# SIPM_readout.net
KiCad netlist of a schematic drawn in EAGLE
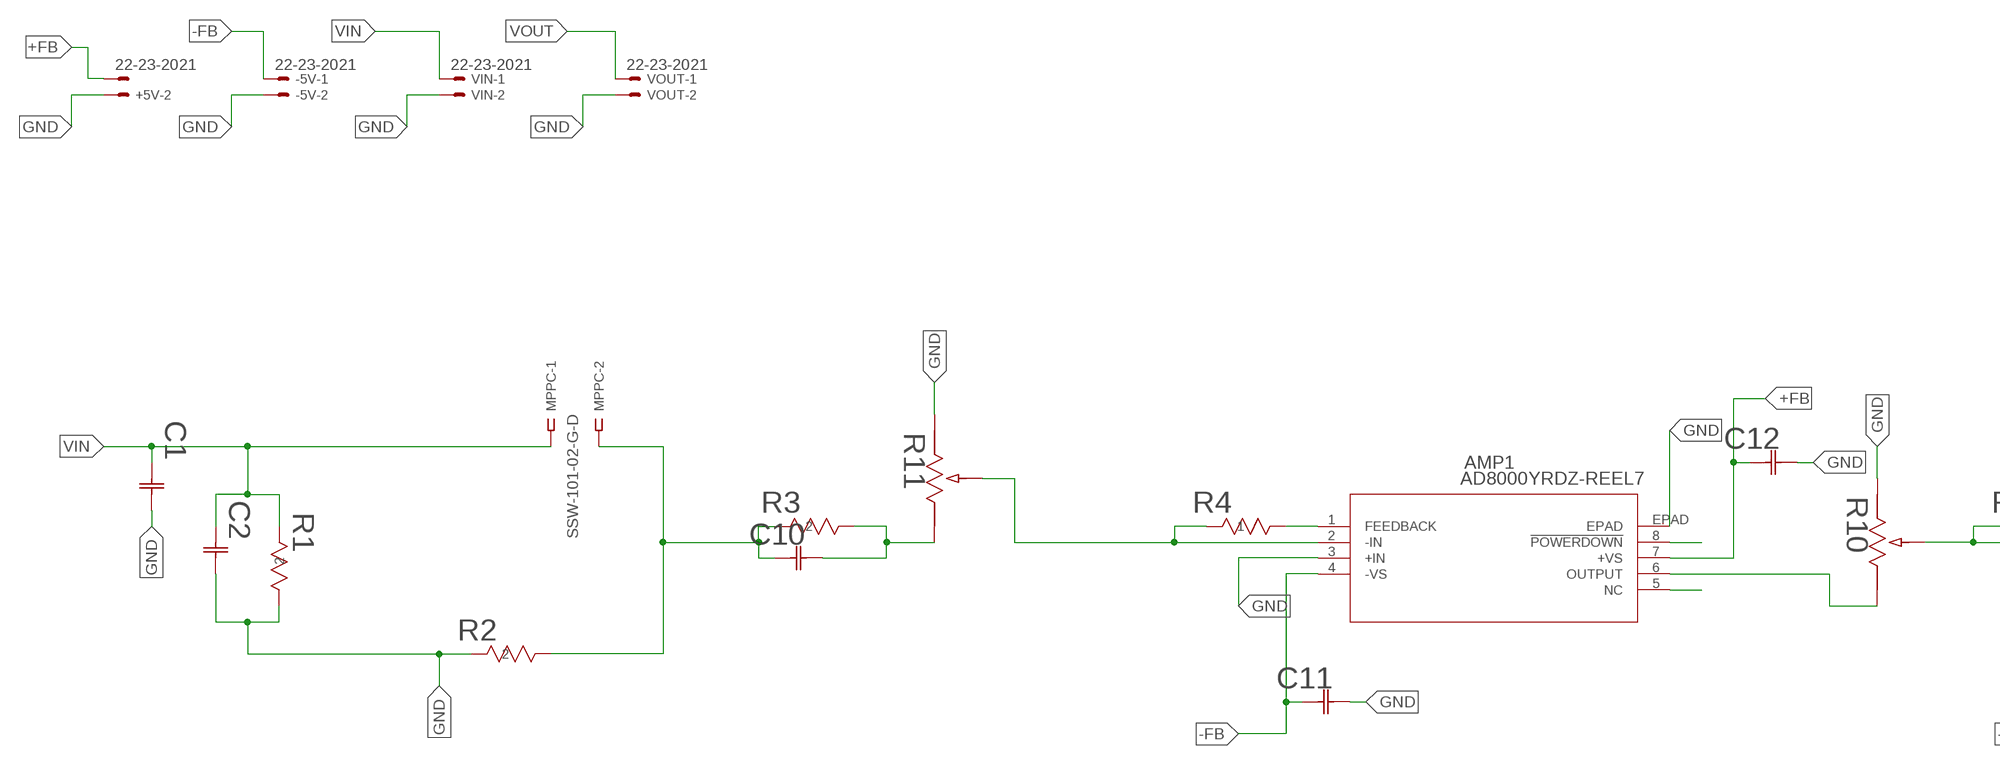
[diagram p0: schematic, sheet 1, part 1 of 2]
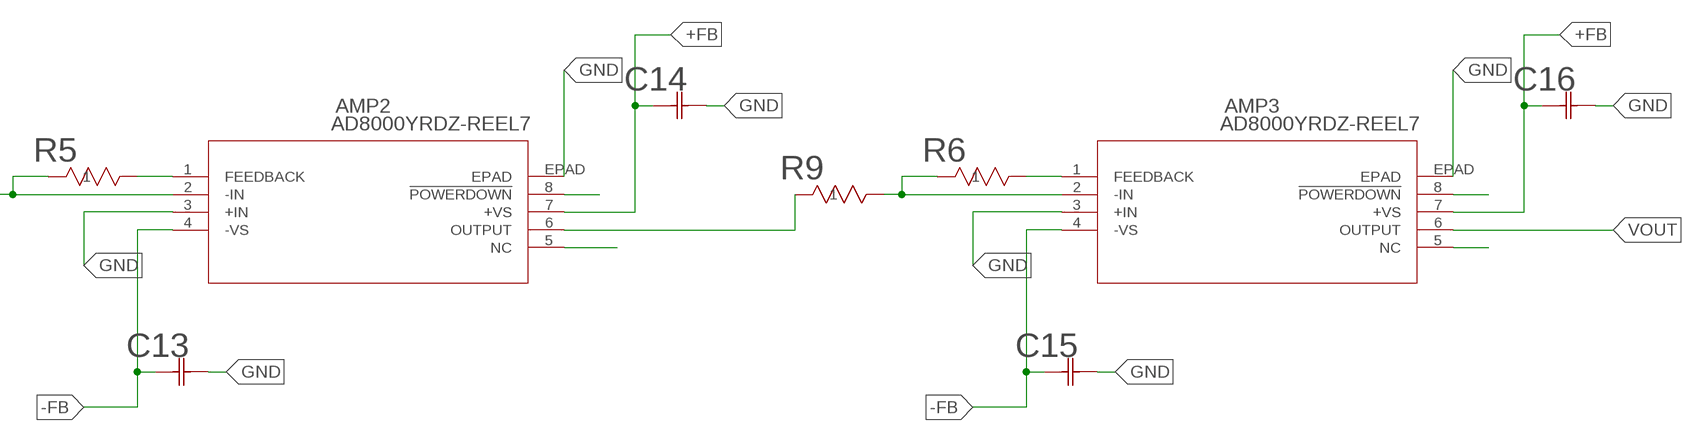
[diagram p1: schematic, sheet 1, part 2 of 2]

(export (version "E")
  (design (tool "Eeschema 10.0.6"))
  (components
    (comp (ref "+5V")
      (value "22-23-2021")
      (footprint "eagle-import:22-23-2021")
      (fields (field (name "MF") "MOLEX"))
      (libsource (lib "eagle-import") (part "22-23-2021"))
    )
    (comp (ref "-5V")
      (value "22-23-2021")
      (footprint "eagle-import:22-23-2021")
      (fields (field (name "MF") "MOLEX"))
      (libsource (lib "eagle-import") (part "22-23-2021"))
    )
    (comp (ref "AMP1")
      (value "AD8000YRDZ-REEL7")
      (footprint "eagle-import:RD_8_1_ADI")
      (fields (field (name "COPYRIGHT") "Copyright (C) 2018 Accelerated Designs. All rights reserved"))
      (libsource (lib "eagle-import") (part "AD8000YRDZ-REEL7"))
    )
    (comp (ref "AMP2")
      (value "AD8000YRDZ-REEL7")
      (footprint "eagle-import:RD_8_1_ADI")
      (fields (field (name "COPYRIGHT") "Copyright (C) 2018 Accelerated Designs. All rights reserved"))
      (libsource (lib "eagle-import") (part "AD8000YRDZ-REEL7"))
    )
    (comp (ref "AMP3")
      (value "AD8000YRDZ-REEL7")
      (footprint "eagle-import:RD_8_1_ADI")
      (fields (field (name "COPYRIGHT") "Copyright (C) 2018 Accelerated Designs. All rights reserved"))
      (libsource (lib "eagle-import") (part "AD8000YRDZ-REEL7"))
    )
    (comp (ref "C1")
      (value "C3225X7S2A335M200ABCAP_3225_TDK-M")
      (footprint "eagle-import:CAP_3225_TDK-M")
      (fields (field (name "MANUFACTURER_PART_NUMBER") "C3225X7S2A335M200AB"))
      (libsource (lib "eagle-import") (part "C3225X7S2A335M200ABCAP_3225_TDK-M"))
    )
    (comp (ref "C2")
      (value "C3225X7R2A105K200AACAP_3225_TDK-M")
      (footprint "eagle-import:CAP_3225_TDK-M")
      (fields (field (name "MANUFACTURER_PART_NUMBER") "C3225X7R2A105K200AA"))
      (libsource (lib "eagle-import") (part "C3225X7R2A105K200AACAP_3225_TDK-M"))
    )
    (comp (ref "C10")
      (value "CGA3E2C0G1H101J080AA")
      (footprint "eagle-import:CAP_1608_TDK")
      (libsource (lib "eagle-import") (part "CGA3E2C0G1H101J080AA"))
    )
    (comp (ref "C11")
      (value "CL10B104KB8NNNL")
      (footprint "eagle-import:CAP_CL10_SAM")
      (fields (field (name "COPYRIGHT") "Copyright (C) 2018 Accelerated Designs. All rights reserved"))
      (libsource (lib "eagle-import") (part "CL10B104KB8NNNL"))
    )
    (comp (ref "C12")
      (value "CL10B104KB8NNNL")
      (footprint "eagle-import:CAP_CL10_SAM")
      (fields (field (name "COPYRIGHT") "Copyright (C) 2018 Accelerated Designs. All rights reserved"))
      (libsource (lib "eagle-import") (part "CL10B104KB8NNNL"))
    )
    (comp (ref "C13")
      (value "CL10B104KB8NNNL")
      (footprint "eagle-import:CAP_CL10_SAM")
      (fields (field (name "COPYRIGHT") "Copyright (C) 2018 Accelerated Designs. All rights reserved"))
      (libsource (lib "eagle-import") (part "CL10B104KB8NNNL"))
    )
    (comp (ref "C14")
      (value "CL10B104KB8NNNL")
      (footprint "eagle-import:CAP_CL10_SAM")
      (fields (field (name "COPYRIGHT") "Copyright (C) 2018 Accelerated Designs. All rights reserved"))
      (libsource (lib "eagle-import") (part "CL10B104KB8NNNL"))
    )
    (comp (ref "C15")
      (value "CL10B104KB8NNNL")
      (footprint "eagle-import:CAP_CL10_SAM")
      (fields (field (name "COPYRIGHT") "Copyright (C) 2018 Accelerated Designs. All rights reserved"))
      (libsource (lib "eagle-import") (part "CL10B104KB8NNNL"))
    )
    (comp (ref "C16")
      (value "CL10B104KB8NNNL")
      (footprint "eagle-import:CAP_CL10_SAM")
      (fields (field (name "COPYRIGHT") "Copyright (C) 2018 Accelerated Designs. All rights reserved"))
      (libsource (lib "eagle-import") (part "CL10B104KB8NNNL"))
    )
    (comp (ref "MPPC")
      (value "SSW-101-02-G-D")
      (footprint "eagle-import:SSW-101-02-G-D")
      (fields (field (name "MF") "Samtec Inc."))
      (libsource (lib "eagle-import") (part "SSW-101-02-G-D"))
    )
    (comp (ref "R1")
      (value "RC0603FR-072ML")
      (footprint "eagle-import:RC0603N_YAG")
      (libsource (lib "eagle-import") (part "RC0603FR-072ML"))
    )
    (comp (ref "R2")
      (value "RT0603BRD0710RL")
      (footprint "eagle-import:RC0603N_YAG")
      (libsource (lib "eagle-import") (part "RT0603BRD0710RL"))
    )
    (comp (ref "R3")
      (value "RT0603BRD0710RL")
      (footprint "eagle-import:RC0603N_YAG")
      (libsource (lib "eagle-import") (part "RT0603BRD0710RL"))
    )
    (comp (ref "R4")
      (value "ESR03EZPF1001")
      (footprint "eagle-import:RES_R0603_ROM")
      (libsource (lib "eagle-import") (part "ESR03EZPF1001"))
    )
    (comp (ref "R5")
      (value "ESR03EZPF1001")
      (footprint "eagle-import:RES_R0603_ROM")
      (libsource (lib "eagle-import") (part "ESR03EZPF1001"))
    )
    (comp (ref "R6")
      (value "ESR03EZPF1001")
      (footprint "eagle-import:RES_R0603_ROM")
      (libsource (lib "eagle-import") (part "ESR03EZPF1001"))
    )
    (comp (ref "R9")
      (value "ESR03EZPF1001")
      (footprint "eagle-import:RES_R0603_ROM")
      (libsource (lib "eagle-import") (part "ESR03EZPF1001"))
    )
    (comp (ref "R10")
      (value "3214W-1-103E")
      (footprint "eagle-import:POT_3214W")
      (libsource (lib "eagle-import") (part "3214W-1-103E"))
    )
    (comp (ref "R11")
      (value "3214W-1-103E")
      (footprint "eagle-import:POT_3214W")
      (libsource (lib "eagle-import") (part "3214W-1-103E"))
    )
    (comp (ref "VIN")
      (value "22-23-2021")
      (footprint "eagle-import:22-23-2021")
      (fields (field (name "MF") "MOLEX"))
      (libsource (lib "eagle-import") (part "22-23-2021"))
    )
    (comp (ref "VOUT")
      (value "22-23-2021")
      (footprint "eagle-import:22-23-2021")
      (fields (field (name "MF") "MOLEX"))
      (libsource (lib "eagle-import") (part "22-23-2021"))
    )
  )
  (nets
    (net (code "1") (name "+FB") (class "Default")
      (node (ref "+5V") (pin "1") (pinfunction "S_1") (pintype "passive"))
      (node (ref "AMP1") (pin "7") (pinfunction "+VS_7") (pintype "power_in"))
      (node (ref "AMP2") (pin "7") (pinfunction "+VS_7") (pintype "power_in"))
      (node (ref "AMP3") (pin "7") (pinfunction "+VS_7") (pintype "power_in"))
      (node (ref "C12") (pin "1") (pinfunction "1_1") (pintype "passive"))
      (node (ref "C14") (pin "1") (pinfunction "1_1") (pintype "passive"))
      (node (ref "C16") (pin "1") (pinfunction "1_1") (pintype "passive"))
    )
    (net (code "2") (name "-FB") (class "Default")
      (node (ref "-5V") (pin "1") (pinfunction "S_1") (pintype "passive"))
      (node (ref "AMP1") (pin "4") (pinfunction "-VS_4") (pintype "power_in"))
      (node (ref "AMP2") (pin "4") (pinfunction "-VS_4") (pintype "power_in"))
      (node (ref "AMP3") (pin "4") (pinfunction "-VS_4") (pintype "power_in"))
      (node (ref "C11") (pin "1") (pinfunction "1_1") (pintype "passive"))
      (node (ref "C13") (pin "1") (pinfunction "1_1") (pintype "passive"))
      (node (ref "C15") (pin "1") (pinfunction "1_1") (pintype "passive"))
    )
    (net (code "3") (name "GND") (class "Default")
      (node (ref "+5V") (pin "2") (pinfunction "S_2") (pintype "passive"))
      (node (ref "-5V") (pin "2") (pinfunction "S_2") (pintype "passive"))
      (node (ref "AMP1") (pin "3") (pinfunction "+IN_3") (pintype "input"))
      (node (ref "AMP1") (pin "EPAD") (pinfunction "EPAD_EPAD") (pintype "passive"))
      (node (ref "AMP2") (pin "3") (pinfunction "+IN_3") (pintype "input"))
      (node (ref "AMP2") (pin "EPAD") (pinfunction "EPAD_EPAD") (pintype "passive"))
      (node (ref "AMP3") (pin "3") (pinfunction "+IN_3") (pintype "input"))
      (node (ref "AMP3") (pin "EPAD") (pinfunction "EPAD_EPAD") (pintype "passive"))
      (node (ref "C1") (pin "2") (pinfunction "2_2") (pintype "passive"))
      (node (ref "C11") (pin "2") (pinfunction "2_2") (pintype "passive"))
      (node (ref "C12") (pin "2") (pinfunction "2_2") (pintype "passive"))
      (node (ref "C13") (pin "2") (pinfunction "2_2") (pintype "passive"))
      (node (ref "C14") (pin "2") (pinfunction "2_2") (pintype "passive"))
      (node (ref "C15") (pin "2") (pinfunction "2_2") (pintype "passive"))
      (node (ref "C16") (pin "2") (pinfunction "2_2") (pintype "passive"))
      (node (ref "C2") (pin "2") (pinfunction "2_2") (pintype "passive"))
      (node (ref "R1") (pin "1") (pinfunction "1_1") (pintype "passive"))
      (node (ref "R10") (pin "1") (pinfunction "1_1") (pintype "passive"))
      (node (ref "R11") (pin "1") (pinfunction "1_1") (pintype "passive"))
      (node (ref "R2") (pin "2") (pinfunction "2_2") (pintype "passive"))
      (node (ref "VIN") (pin "2") (pinfunction "S_2") (pintype "passive"))
      (node (ref "VOUT") (pin "2") (pinfunction "S_2") (pintype "passive"))
    )
    (net (code "4") (name "Net-(AMP1--IN)") (class "Default")
      (node (ref "AMP1") (pin "2") (pinfunction "-IN_2") (pintype "input"))
      (node (ref "R11") (pin "2") (pinfunction "2_2") (pintype "passive"))
      (node (ref "R4") (pin "1") (pinfunction "1_1") (pintype "passive"))
    )
    (net (code "5") (name "Net-(AMP1-FEEDBACK)") (class "Default")
      (node (ref "AMP1") (pin "1") (pinfunction "FEEDBACK_1") (pintype "passive"))
      (node (ref "R4") (pin "2") (pinfunction "2_2") (pintype "passive"))
    )
    (net (code "6") (name "Net-(AMP1-OUTPUT)") (class "Default")
      (node (ref "AMP1") (pin "6") (pinfunction "OUTPUT_6") (pintype "output"))
      (node (ref "R10") (pin "3") (pinfunction "3_3") (pintype "passive"))
    )
    (net (code "7") (name "Net-(AMP2--IN)") (class "Default")
      (node (ref "AMP2") (pin "2") (pinfunction "-IN_2") (pintype "input"))
      (node (ref "R10") (pin "2") (pinfunction "2_2") (pintype "passive"))
      (node (ref "R5") (pin "1") (pinfunction "1_1") (pintype "passive"))
    )
    (net (code "8") (name "Net-(AMP2-FEEDBACK)") (class "Default")
      (node (ref "AMP2") (pin "1") (pinfunction "FEEDBACK_1") (pintype "passive"))
      (node (ref "R5") (pin "2") (pinfunction "2_2") (pintype "passive"))
    )
    (net (code "9") (name "Net-(AMP2-OUTPUT)") (class "Default")
      (node (ref "AMP2") (pin "6") (pinfunction "OUTPUT_6") (pintype "output"))
      (node (ref "R9") (pin "1") (pinfunction "1_1") (pintype "passive"))
    )
    (net (code "10") (name "Net-(AMP3--IN)") (class "Default")
      (node (ref "AMP3") (pin "2") (pinfunction "-IN_2") (pintype "input"))
      (node (ref "R6") (pin "1") (pinfunction "1_1") (pintype "passive"))
      (node (ref "R9") (pin "2") (pinfunction "2_2") (pintype "passive"))
    )
    (net (code "11") (name "Net-(AMP3-FEEDBACK)") (class "Default")
      (node (ref "AMP3") (pin "1") (pinfunction "FEEDBACK_1") (pintype "passive"))
      (node (ref "R6") (pin "2") (pinfunction "2_2") (pintype "passive"))
    )
    (net (code "12") (name "Net-(C10-Pad2)") (class "Default")
      (node (ref "C10") (pin "2") (pinfunction "2_2") (pintype "passive"))
      (node (ref "R11") (pin "3") (pinfunction "3_3") (pintype "passive"))
      (node (ref "R3") (pin "1") (pinfunction "1_1") (pintype "passive"))
    )
    (net (code "13") (name "Net-(MPPCB-1)") (class "Default")
      (node (ref "C10") (pin "1") (pinfunction "1_1") (pintype "passive"))
      (node (ref "MPPC") (pin "2") (pinfunction "1_2") (pintype "passive"))
      (node (ref "R2") (pin "1") (pinfunction "1_1") (pintype "passive"))
      (node (ref "R3") (pin "2") (pinfunction "2_2") (pintype "passive"))
    )
    (net (code "14") (name "VIN") (class "Default")
      (node (ref "C1") (pin "1") (pinfunction "1_1") (pintype "passive"))
      (node (ref "C2") (pin "1") (pinfunction "1_1") (pintype "passive"))
      (node (ref "MPPC") (pin "1") (pinfunction "1_1") (pintype "passive"))
      (node (ref "R1") (pin "2") (pinfunction "2_2") (pintype "passive"))
      (node (ref "VIN") (pin "1") (pinfunction "S_1") (pintype "passive"))
    )
    (net (code "15") (name "VOUT") (class "Default")
      (node (ref "AMP3") (pin "6") (pinfunction "OUTPUT_6") (pintype "output"))
      (node (ref "VOUT") (pin "1") (pinfunction "S_1") (pintype "passive"))
    )
    (net (code "16") (name "unconnected-(AMP1-NC-Pad5)") (class "Default")
      (node (ref "AMP1") (pin "5") (pinfunction "NC_5") (pintype "no_connect"))
    )
    (net (code "17") (name "unconnected-(AMP1-~{POWERDOWN}-Pad8)") (class "Default")
      (node (ref "AMP1") (pin "8") (pinfunction "~{POWERDOWN}_8") (pintype "passive"))
    )
    (net (code "18") (name "unconnected-(AMP2-NC-Pad5)") (class "Default")
      (node (ref "AMP2") (pin "5") (pinfunction "NC_5") (pintype "no_connect"))
    )
    (net (code "19") (name "unconnected-(AMP2-~{POWERDOWN}-Pad8)") (class "Default")
      (node (ref "AMP2") (pin "8") (pinfunction "~{POWERDOWN}_8") (pintype "passive"))
    )
    (net (code "20") (name "unconnected-(AMP3-NC-Pad5)") (class "Default")
      (node (ref "AMP3") (pin "5") (pinfunction "NC_5") (pintype "no_connect"))
    )
    (net (code "21") (name "unconnected-(AMP3-~{POWERDOWN}-Pad8)") (class "Default")
      (node (ref "AMP3") (pin "8") (pinfunction "~{POWERDOWN}_8") (pintype "passive"))
    )
  )
)
